# schematic.net
KiCad netlist of a schematic drawn in EAGLE
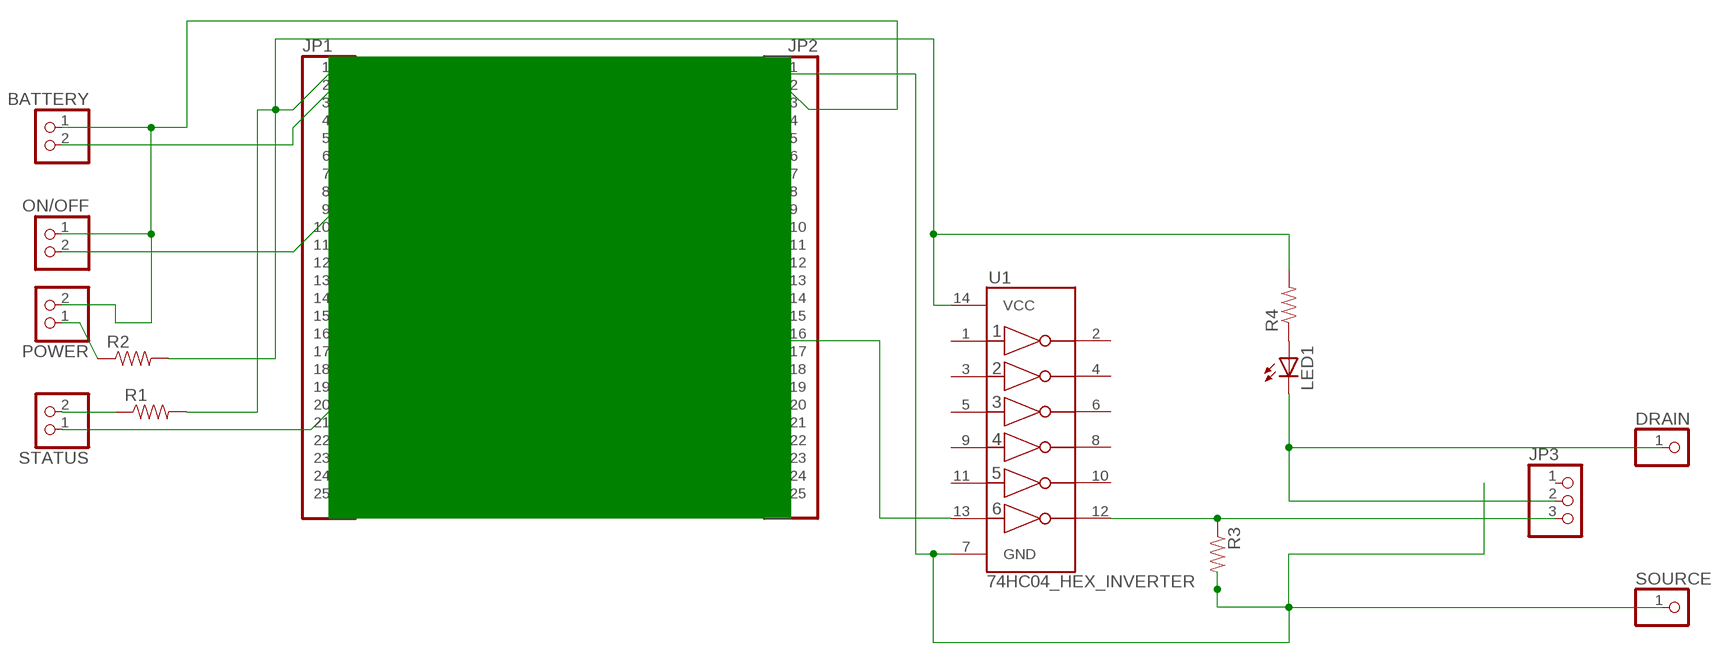
[diagram p0: schematic, sheet 1]

(export (version "E")
  (design (tool "Eeschema 10.0.6"))
  (components
    (comp (ref "BATTERY")
      (value "PINHD-1X2")
      (footprint "eagle-import:1X02")
      (libsource (lib "eagle-import") (part "PINHD-1X2"))
    )
    (comp (ref "DRAIN")
      (value "PINHD-1X1")
      (footprint "eagle-import:1X01")
      (libsource (lib "eagle-import") (part "PINHD-1X1"))
    )
    (comp (ref "JP1")
      (value "PINHD-1X25")
      (footprint "eagle-import:1X25")
      (libsource (lib "eagle-import") (part "PINHD-1X25"))
    )
    (comp (ref "JP2")
      (value "PINHD-1X25")
      (footprint "eagle-import:1X25")
      (libsource (lib "eagle-import") (part "PINHD-1X25"))
    )
    (comp (ref "JP3")
      (value "PINHD-1X3")
      (footprint "eagle-import:1X03")
      (libsource (lib "eagle-import") (part "PINHD-1X3"))
    )
    (comp (ref "LED1")
      (value "LED-3MM-NO_SILK")
      (footprint "eagle-import:LED3MM-NS")
      (libsource (lib "eagle-import") (part "LED-3MM-NO_SILK"))
    )
    (comp (ref "ON/OFF")
      (value "PINHD-1X2")
      (footprint "eagle-import:1X02")
      (libsource (lib "eagle-import") (part "PINHD-1X2"))
    )
    (comp (ref "POWER")
      (value "PINHD-1X2")
      (footprint "eagle-import:1X02")
      (libsource (lib "eagle-import") (part "PINHD-1X2"))
    )
    (comp (ref "R1")
      (value "RESISTORKIT")
      (footprint "eagle-import:AXIAL-0.3-KIT")
      (libsource (lib "eagle-import") (part "RESISTORKIT"))
    )
    (comp (ref "R2")
      (value "RESISTORKIT")
      (footprint "eagle-import:AXIAL-0.3-KIT")
      (libsource (lib "eagle-import") (part "RESISTORKIT"))
    )
    (comp (ref "R3")
      (value "RESISTORKIT")
      (footprint "eagle-import:AXIAL-0.3-KIT")
      (libsource (lib "eagle-import") (part "RESISTORKIT"))
    )
    (comp (ref "R4")
      (value "RESISTORKIT")
      (footprint "eagle-import:AXIAL-0.3-KIT")
      (libsource (lib "eagle-import") (part "RESISTORKIT"))
    )
    (comp (ref "SOURCE")
      (value "PINHD-1X1")
      (footprint "eagle-import:1X01")
      (libsource (lib "eagle-import") (part "PINHD-1X1"))
    )
    (comp (ref "STATUS")
      (value "PINHD-1X2")
      (footprint "eagle-import:1X02")
      (libsource (lib "eagle-import") (part "PINHD-1X2"))
    )
    (comp (ref "U1")
      (value "74HC04_HEX_INVERTER")
      (footprint "eagle-import:DIL14")
      (libsource (lib "eagle-import") (part "74HC04_HEX_INVERTER"))
    )
  )
  (nets
    (net (code "1") (name "Net-(BATTERY-Pad1)") (class "Default")
      (node (ref "BATTERY") (pin "1") (pinfunction "1_1") (pintype "passive"))
      (node (ref "JP2") (pin "2") (pinfunction "2_2") (pintype "passive"))
      (node (ref "ON/OFF") (pin "1") (pinfunction "1_1") (pintype "passive"))
      (node (ref "POWER") (pin "2") (pinfunction "2_2") (pintype "passive"))
    )
    (net (code "2") (name "Net-(BATTERY-Pad2)") (class "Default")
      (node (ref "BATTERY") (pin "2") (pinfunction "2_2") (pintype "passive"))
      (node (ref "JP1") (pin "2") (pinfunction "2_2") (pintype "passive"))
    )
    (net (code "3") (name "Net-(JP1-Pad9)") (class "Default")
      (node (ref "JP1") (pin "9") (pinfunction "9_9") (pintype "passive"))
      (node (ref "ON/OFF") (pin "2") (pinfunction "2_2") (pintype "passive"))
    )
    (net (code "4") (name "Net-(JP1-Pad20)") (class "Default")
      (node (ref "JP1") (pin "20") (pinfunction "20_20") (pintype "passive"))
      (node (ref "STATUS") (pin "1") (pinfunction "1_1") (pintype "passive"))
    )
    (net (code "5") (name "Net-(LED1-C)") (class "Default")
      (node (ref "DRAIN") (pin "1") (pinfunction "1_1") (pintype "passive"))
      (node (ref "JP3") (pin "2") (pinfunction "2_2") (pintype "passive"))
      (node (ref "LED1") (pin "K") (pinfunction "C_K") (pintype "passive"))
    )
    (net (code "6") (name "Net-(R1-1)") (class "Default")
      (node (ref "R1") (pin "P$1") (pinfunction "1_P$1") (pintype "passive"))
      (node (ref "STATUS") (pin "2") (pinfunction "2_2") (pintype "passive"))
    )
    (net (code "7") (name "Net-(R1-2)") (class "Default")
      (node (ref "JP1") (pin "1") (pinfunction "1_1") (pintype "passive"))
      (node (ref "R1") (pin "P$2") (pinfunction "2_P$2") (pintype "passive"))
      (node (ref "R2") (pin "P$2") (pinfunction "2_P$2") (pintype "passive"))
      (node (ref "R4") (pin "P$2") (pinfunction "2_P$2") (pintype "passive"))
      (node (ref "U1") (pin "14") (pinfunction "VCC_14") (pintype "power_in"))
    )
    (net (code "8") (name "Net-(R2-1)") (class "Default")
      (node (ref "POWER") (pin "1") (pinfunction "1_1") (pintype "passive"))
      (node (ref "R2") (pin "P$1") (pinfunction "1_P$1") (pintype "passive"))
    )
    (net (code "9") (name "Net-(R3-1)") (class "Default")
      (node (ref "JP3") (pin "3") (pinfunction "3_3") (pintype "passive"))
      (node (ref "R3") (pin "P$1") (pinfunction "1_P$1") (pintype "passive"))
      (node (ref "U1") (pin "12") (pinfunction "6Y_12") (pintype "output"))
    )
    (net (code "10") (name "Net-(R3-2)") (class "Default")
      (node (ref "JP2") (pin "1") (pinfunction "1_1") (pintype "passive"))
      (node (ref "R3") (pin "P$2") (pinfunction "2_P$2") (pintype "passive"))
      (node (ref "SOURCE") (pin "1") (pinfunction "1_1") (pintype "passive"))
      (node (ref "U1") (pin "7") (pinfunction "GND_7") (pintype "power_in"))
    )
    (net (code "11") (name "Net-(R4-1)") (class "Default")
      (node (ref "LED1") (pin "A") (pinfunction "A_A") (pintype "passive"))
      (node (ref "R4") (pin "P$1") (pinfunction "1_P$1") (pintype "passive"))
    )
    (net (code "12") (name "Net-(U1-6A)") (class "Default")
      (node (ref "JP2") (pin "16") (pinfunction "16_16") (pintype "passive"))
      (node (ref "U1") (pin "13") (pinfunction "6A_13") (pintype "input"))
    )
    (net (code "13") (name "unconnected-(JP1-Pad3)") (class "Default")
      (node (ref "JP1") (pin "3") (pinfunction "3_3") (pintype "passive"))
    )
    (net (code "14") (name "unconnected-(JP1-Pad4)") (class "Default")
      (node (ref "JP1") (pin "4") (pinfunction "4_4") (pintype "passive"))
    )
    (net (code "15") (name "unconnected-(JP1-Pad5)") (class "Default")
      (node (ref "JP1") (pin "5") (pinfunction "5_5") (pintype "passive"))
    )
    (net (code "16") (name "unconnected-(JP1-Pad6)") (class "Default")
      (node (ref "JP1") (pin "6") (pinfunction "6_6") (pintype "passive"))
    )
    (net (code "17") (name "unconnected-(JP1-Pad7)") (class "Default")
      (node (ref "JP1") (pin "7") (pinfunction "7_7") (pintype "passive"))
    )
    (net (code "18") (name "unconnected-(JP1-Pad8)") (class "Default")
      (node (ref "JP1") (pin "8") (pinfunction "8_8") (pintype "passive"))
    )
    (net (code "19") (name "unconnected-(JP1-Pad10)") (class "Default")
      (node (ref "JP1") (pin "10") (pinfunction "10_10") (pintype "passive"))
    )
    (net (code "20") (name "unconnected-(JP1-Pad11)") (class "Default")
      (node (ref "JP1") (pin "11") (pinfunction "11_11") (pintype "passive"))
    )
    (net (code "21") (name "unconnected-(JP1-Pad12)") (class "Default")
      (node (ref "JP1") (pin "12") (pinfunction "12_12") (pintype "passive"))
    )
    (net (code "22") (name "unconnected-(JP1-Pad13)") (class "Default")
      (node (ref "JP1") (pin "13") (pinfunction "13_13") (pintype "passive"))
    )
    (net (code "23") (name "unconnected-(JP1-Pad14)") (class "Default")
      (node (ref "JP1") (pin "14") (pinfunction "14_14") (pintype "passive"))
    )
    (net (code "24") (name "unconnected-(JP1-Pad15)") (class "Default")
      (node (ref "JP1") (pin "15") (pinfunction "15_15") (pintype "passive"))
    )
    (net (code "25") (name "unconnected-(JP1-Pad16)") (class "Default")
      (node (ref "JP1") (pin "16") (pinfunction "16_16") (pintype "passive"))
    )
    (net (code "26") (name "unconnected-(JP1-Pad17)") (class "Default")
      (node (ref "JP1") (pin "17") (pinfunction "17_17") (pintype "passive"))
    )
    (net (code "27") (name "unconnected-(JP1-Pad18)") (class "Default")
      (node (ref "JP1") (pin "18") (pinfunction "18_18") (pintype "passive"))
    )
    (net (code "28") (name "unconnected-(JP1-Pad19)") (class "Default")
      (node (ref "JP1") (pin "19") (pinfunction "19_19") (pintype "passive"))
    )
    (net (code "29") (name "unconnected-(JP1-Pad21)") (class "Default")
      (node (ref "JP1") (pin "21") (pinfunction "21_21") (pintype "passive"))
    )
    (net (code "30") (name "unconnected-(JP1-Pad22)") (class "Default")
      (node (ref "JP1") (pin "22") (pinfunction "22_22") (pintype "passive"))
    )
    (net (code "31") (name "unconnected-(JP1-Pad23)") (class "Default")
      (node (ref "JP1") (pin "23") (pinfunction "23_23") (pintype "passive"))
    )
    (net (code "32") (name "unconnected-(JP1-Pad24)") (class "Default")
      (node (ref "JP1") (pin "24") (pinfunction "24_24") (pintype "passive"))
    )
    (net (code "33") (name "unconnected-(JP1-Pad25)") (class "Default")
      (node (ref "JP1") (pin "25") (pinfunction "25_25") (pintype "passive"))
    )
    (net (code "34") (name "unconnected-(JP2-Pad3)") (class "Default")
      (node (ref "JP2") (pin "3") (pinfunction "3_3") (pintype "passive"))
    )
    (net (code "35") (name "unconnected-(JP2-Pad4)") (class "Default")
      (node (ref "JP2") (pin "4") (pinfunction "4_4") (pintype "passive"))
    )
    (net (code "36") (name "unconnected-(JP2-Pad5)") (class "Default")
      (node (ref "JP2") (pin "5") (pinfunction "5_5") (pintype "passive"))
    )
    (net (code "37") (name "unconnected-(JP2-Pad6)") (class "Default")
      (node (ref "JP2") (pin "6") (pinfunction "6_6") (pintype "passive"))
    )
    (net (code "38") (name "unconnected-(JP2-Pad7)") (class "Default")
      (node (ref "JP2") (pin "7") (pinfunction "7_7") (pintype "passive"))
    )
    (net (code "39") (name "unconnected-(JP2-Pad8)") (class "Default")
      (node (ref "JP2") (pin "8") (pinfunction "8_8") (pintype "passive"))
    )
    (net (code "40") (name "unconnected-(JP2-Pad9)") (class "Default")
      (node (ref "JP2") (pin "9") (pinfunction "9_9") (pintype "passive"))
    )
    (net (code "41") (name "unconnected-(JP2-Pad10)") (class "Default")
      (node (ref "JP2") (pin "10") (pinfunction "10_10") (pintype "passive"))
    )
    (net (code "42") (name "unconnected-(JP2-Pad11)") (class "Default")
      (node (ref "JP2") (pin "11") (pinfunction "11_11") (pintype "passive"))
    )
    (net (code "43") (name "unconnected-(JP2-Pad12)") (class "Default")
      (node (ref "JP2") (pin "12") (pinfunction "12_12") (pintype "passive"))
    )
    (net (code "44") (name "unconnected-(JP2-Pad13)") (class "Default")
      (node (ref "JP2") (pin "13") (pinfunction "13_13") (pintype "passive"))
    )
    (net (code "45") (name "unconnected-(JP2-Pad14)") (class "Default")
      (node (ref "JP2") (pin "14") (pinfunction "14_14") (pintype "passive"))
    )
    (net (code "46") (name "unconnected-(JP2-Pad15)") (class "Default")
      (node (ref "JP2") (pin "15") (pinfunction "15_15") (pintype "passive"))
    )
    (net (code "47") (name "unconnected-(JP2-Pad17)") (class "Default")
      (node (ref "JP2") (pin "17") (pinfunction "17_17") (pintype "passive"))
    )
    (net (code "48") (name "unconnected-(JP2-Pad18)") (class "Default")
      (node (ref "JP2") (pin "18") (pinfunction "18_18") (pintype "passive"))
    )
    (net (code "49") (name "unconnected-(JP2-Pad19)") (class "Default")
      (node (ref "JP2") (pin "19") (pinfunction "19_19") (pintype "passive"))
    )
    (net (code "50") (name "unconnected-(JP2-Pad20)") (class "Default")
      (node (ref "JP2") (pin "20") (pinfunction "20_20") (pintype "passive"))
    )
    (net (code "51") (name "unconnected-(JP2-Pad21)") (class "Default")
      (node (ref "JP2") (pin "21") (pinfunction "21_21") (pintype "passive"))
    )
    (net (code "52") (name "unconnected-(JP2-Pad22)") (class "Default")
      (node (ref "JP2") (pin "22") (pinfunction "22_22") (pintype "passive"))
    )
    (net (code "53") (name "unconnected-(JP2-Pad23)") (class "Default")
      (node (ref "JP2") (pin "23") (pinfunction "23_23") (pintype "passive"))
    )
    (net (code "54") (name "unconnected-(JP2-Pad24)") (class "Default")
      (node (ref "JP2") (pin "24") (pinfunction "24_24") (pintype "passive"))
    )
    (net (code "55") (name "unconnected-(JP2-Pad25)") (class "Default")
      (node (ref "JP2") (pin "25") (pinfunction "25_25") (pintype "passive"))
    )
    (net (code "56") (name "unconnected-(JP3-Pad1)") (class "Default")
      (node (ref "JP3") (pin "1") (pinfunction "1_1") (pintype "passive"))
    )
    (net (code "57") (name "unconnected-(U1-1A-Pad1)") (class "Default")
      (node (ref "U1") (pin "1") (pinfunction "1A_1") (pintype "input"))
    )
    (net (code "58") (name "unconnected-(U1-1Y-Pad2)") (class "Default")
      (node (ref "U1") (pin "2") (pinfunction "1Y_2") (pintype "output"))
    )
    (net (code "59") (name "unconnected-(U1-2A-Pad3)") (class "Default")
      (node (ref "U1") (pin "3") (pinfunction "2A_3") (pintype "input"))
    )
    (net (code "60") (name "unconnected-(U1-2Y-Pad4)") (class "Default")
      (node (ref "U1") (pin "4") (pinfunction "2Y_4") (pintype "output"))
    )
    (net (code "61") (name "unconnected-(U1-3A-Pad5)") (class "Default")
      (node (ref "U1") (pin "5") (pinfunction "3A_5") (pintype "input"))
    )
    (net (code "62") (name "unconnected-(U1-3Y-Pad6)") (class "Default")
      (node (ref "U1") (pin "6") (pinfunction "3Y_6") (pintype "output"))
    )
    (net (code "63") (name "unconnected-(U1-4A-Pad9)") (class "Default")
      (node (ref "U1") (pin "9") (pinfunction "4A_9") (pintype "input"))
    )
    (net (code "64") (name "unconnected-(U1-4Y-Pad8)") (class "Default")
      (node (ref "U1") (pin "8") (pinfunction "4Y_8") (pintype "output"))
    )
    (net (code "65") (name "unconnected-(U1-5A-Pad11)") (class "Default")
      (node (ref "U1") (pin "11") (pinfunction "5A_11") (pintype "input"))
    )
    (net (code "66") (name "unconnected-(U1-5Y-Pad10)") (class "Default")
      (node (ref "U1") (pin "10") (pinfunction "5Y_10") (pintype "output"))
    )
  )
)
